# PROC051C_Decoupling_Caps_Reference.net
KiCad netlist of a schematic drawn in Altium Designer
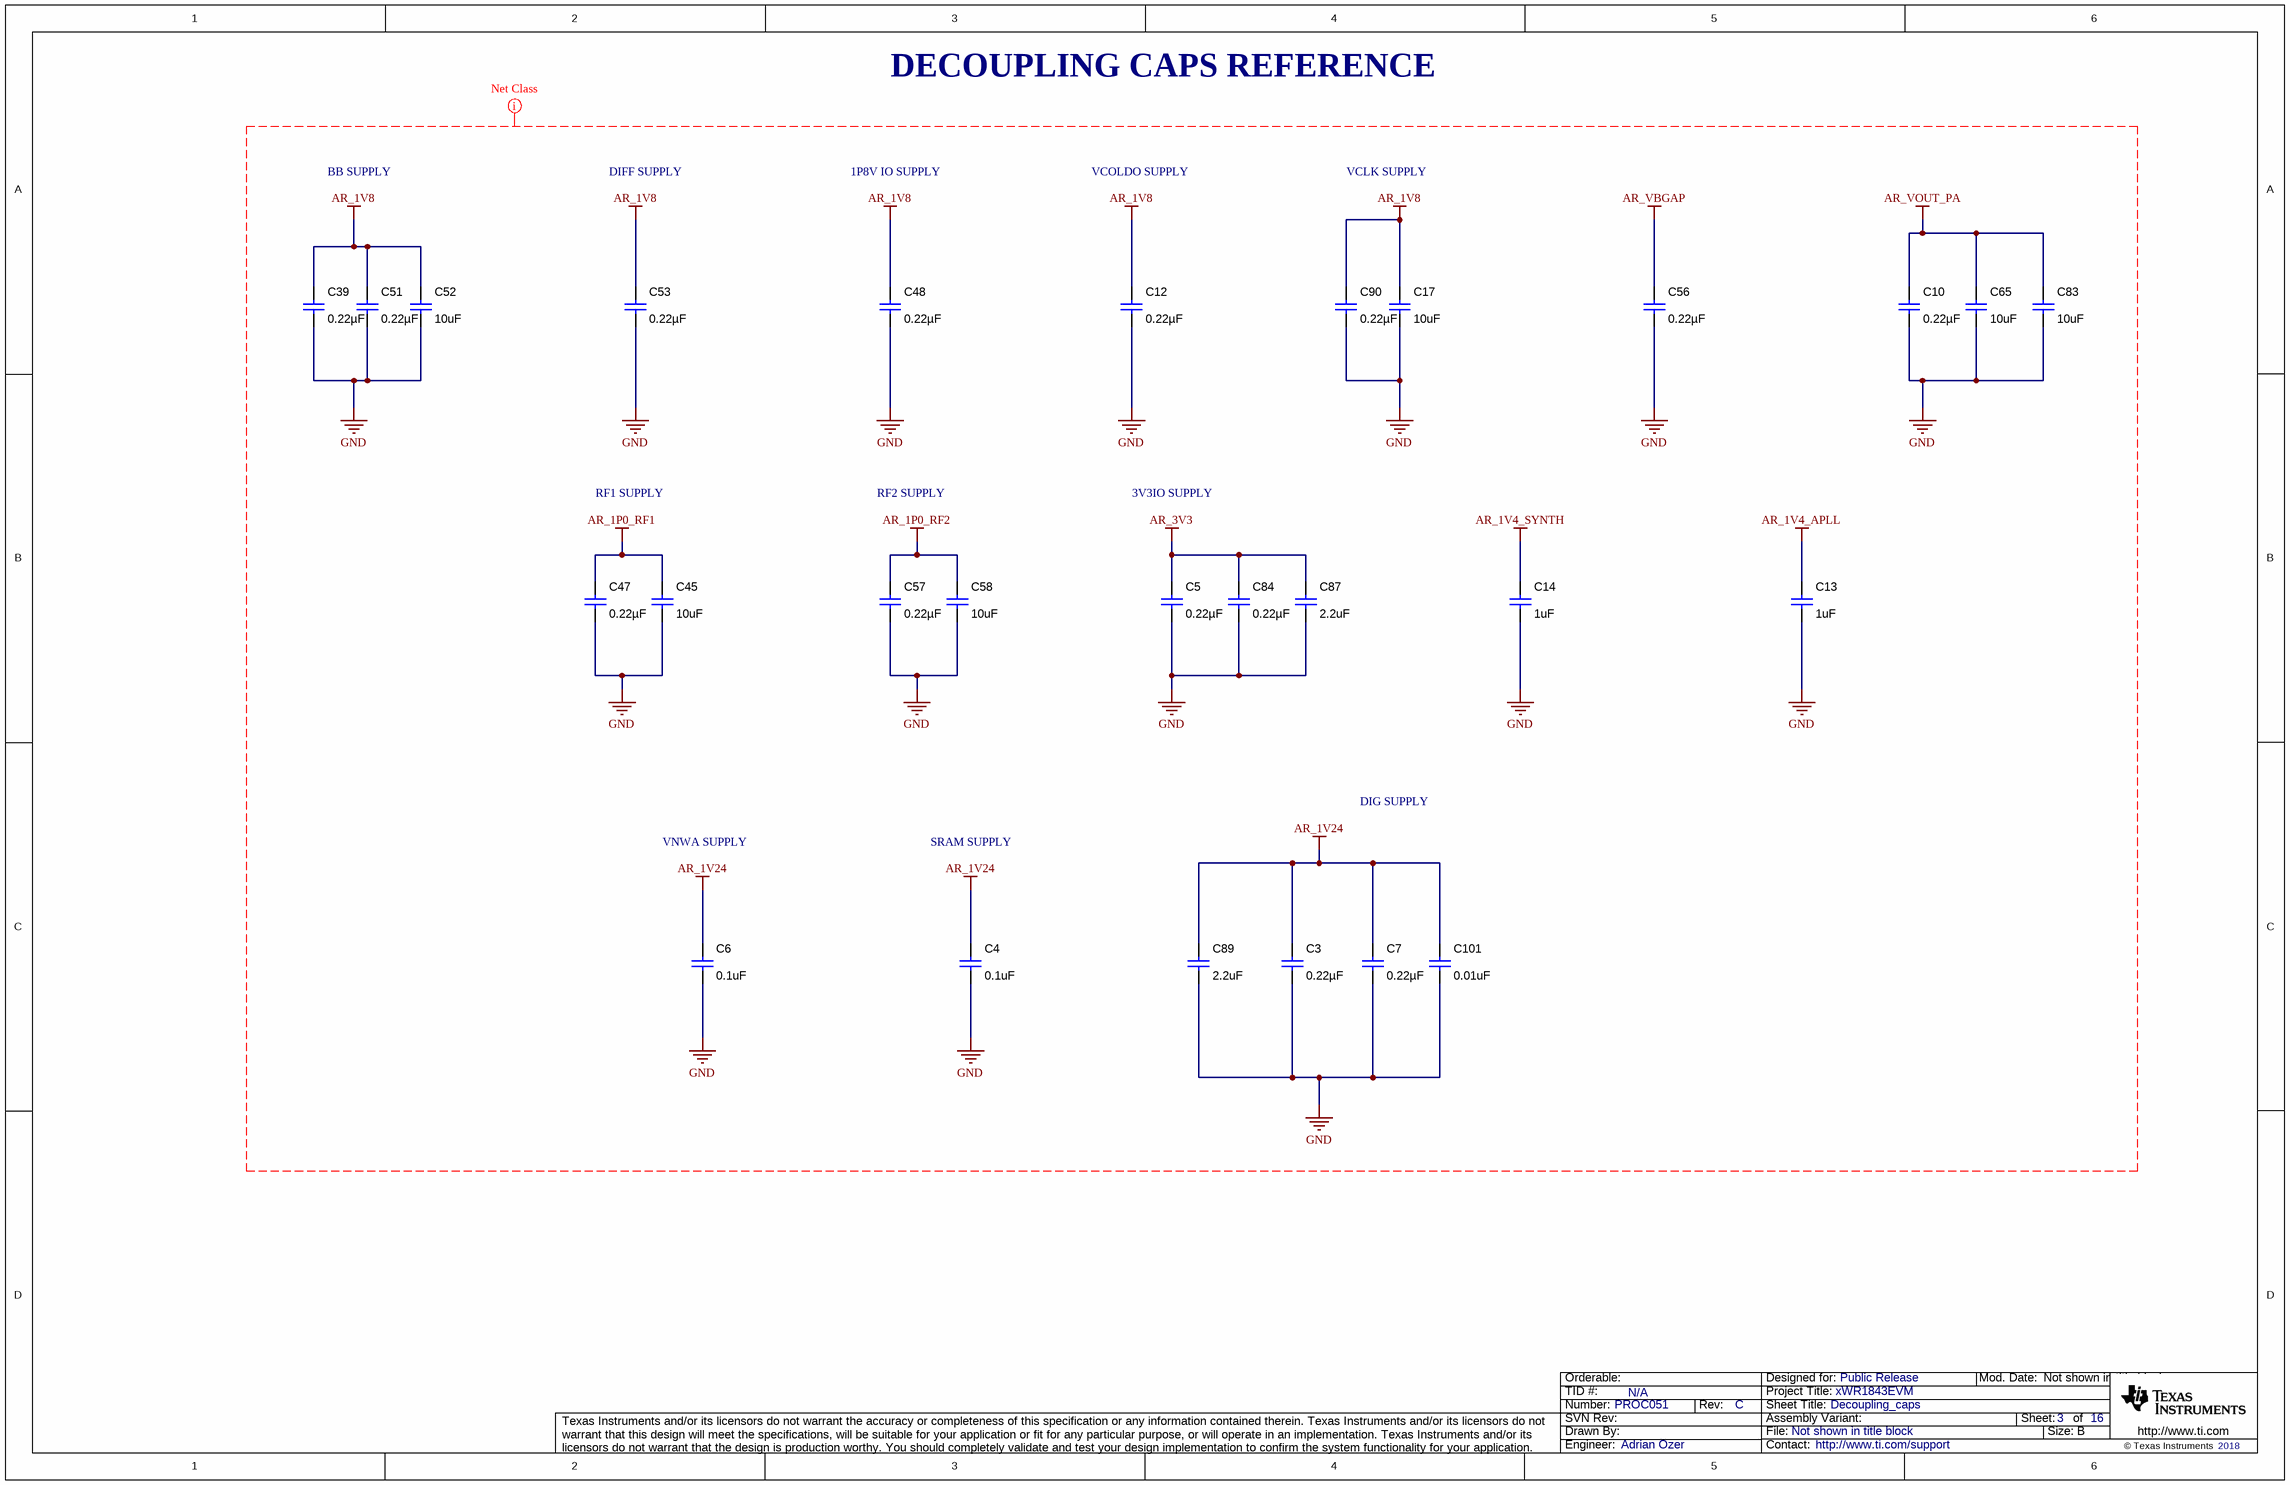
[diagram p0: PROC051C_Decoupling_Caps_Reference.SchDoc]

(export (version "E")
  (design (tool "Eeschema 10.0.6"))
  (components
    (comp (ref "C3")
      (value "GCM155R71C224KE02D")
      (footprint "0402L")
      (description "CAP, CERM, 0.22 µF, 16 V,+/- 10%, X7R, AEC-Q200 Grade 1, 0402")
      (fields (field (name "MANUFACTURER") "MuRata") (field (name "VALUEDISPLAYED") "0.22µF"))
      (libsource (lib "Altium Vault - TI") (part "CMP-0078265-1"))
    )
    (comp (ref "C4")
      (value "GCM155R71C104KA55D")
      (footprint "0402L")
      (description "CAP, CERM, 0.1 uF, 16 V, +/- 10%, X7R, 0402")
      (fields
        (field (name "MANUFACTURER") "MuRata")
        (field (name "VALUEDISPLAYED") "0.1uF")
        (field (name "PUBLISHER") "Texas Instruments")
      )
      (libsource (lib "Altium Vault - TI") (part "CMP-0006351-2"))
    )
    (comp (ref "C5")
      (value "GCM155R71C224KE02D")
      (footprint "0402L")
      (description "CAP, CERM, 0.22 µF, 16 V,+/- 10%, X7R, AEC-Q200 Grade 1, 0402")
      (fields (field (name "MANUFACTURER") "MuRata") (field (name "VALUEDISPLAYED") "0.22µF"))
      (libsource (lib "Altium Vault - TI") (part "CMP-0078265-1"))
    )
    (comp (ref "C6")
      (value "GCM155R71C104KA55D")
      (footprint "0402L")
      (description "CAP, CERM, 0.1 uF, 16 V, +/- 10%, X7R, 0402")
      (fields
        (field (name "MANUFACTURER") "MuRata")
        (field (name "VALUEDISPLAYED") "0.1uF")
        (field (name "PUBLISHER") "Texas Instruments")
      )
      (libsource (lib "Altium Vault - TI") (part "Capacitor"))
    )
    (comp (ref "C7")
      (value "GCM155R71C224KE02D")
      (footprint "0402L")
      (description "CAP, CERM, 0.22 µF, 16 V,+/- 10%, X7R, AEC-Q200 Grade 1, 0402")
      (fields (field (name "MANUFACTURER") "MuRata") (field (name "VALUEDISPLAYED") "0.22µF"))
      (libsource (lib "Altium Vault - TI") (part "CMP-0078265-1"))
    )
    (comp (ref "C10")
      (value "GCM155R71C224KE02D")
      (footprint "0402L")
      (description "CAP, CERM, 0.22 µF, 16 V,+/- 10%, X7R, AEC-Q200 Grade 1, 0402")
      (fields (field (name "MANUFACTURER") "MuRata") (field (name "VALUEDISPLAYED") "0.22µF"))
      (libsource (lib "Altium Vault - TI") (part "CMP-0078265-1"))
    )
    (comp (ref "C12")
      (value "GCM155R71C224KE02D")
      (footprint "0402L")
      (description "CAP, CERM, 0.22 µF, 16 V,+/- 10%, X7R, AEC-Q200 Grade 1, 0402")
      (fields (field (name "MANUFACTURER") "MuRata") (field (name "VALUEDISPLAYED") "0.22µF"))
      (libsource (lib "Altium Vault - TI") (part "CMP-0078265-1"))
    )
    (comp (ref "C13")
      (value "GCM188R71C105KA64D")
      (footprint "0603")
      (description "CAP, CERM, 1 uF, 16 V, +/- 10%, X7R, AEC-Q200 Grade 1, 0603")
      (fields
        (field (name "MANUFACTURER") "MuRata")
        (field (name "VALUEDISPLAYED") "1uF")
        (field (name "PUBLISHER") "Texas Instruments")
      )
      (libsource (lib "Altium Vault - TI") (part "Capacitor"))
    )
    (comp (ref "C14")
      (value "GCM188R71C105KA64D")
      (footprint "0603")
      (description "CAP, CERM, 1 uF, 16 V, +/- 10%, X7R, AEC-Q200 Grade 1, 0603")
      (fields
        (field (name "MANUFACTURER") "MuRata")
        (field (name "VALUEDISPLAYED") "1uF")
        (field (name "PUBLISHER") "Texas Instruments")
      )
      (libsource (lib "Altium Vault - TI") (part "CMP-0007136-5"))
    )
    (comp (ref "C17")
      (value "GCM21BR71A106KE22L")
      (footprint "0805_HV")
      (description "CAP, CERM, 10 uF, 10 V, +/- 10%, X7R, 0805")
      (fields
        (field (name "MANUFACTURER") "MuRata")
        (field (name "VALUEDISPLAYED") "10uF")
        (field (name "PUBLISHER") "Texas Instruments")
      )
      (libsource (lib "Altium Vault - TI") (part "CMP-0008017-2"))
    )
    (comp (ref "C39")
      (value "GCM155R71C224KE02D")
      (footprint "0402L")
      (description "CAP, CERM, 0.22 µF, 16 V,+/- 10%, X7R, AEC-Q200 Grade 1, 0402")
      (fields (field (name "MANUFACTURER") "MuRata") (field (name "VALUEDISPLAYED") "0.22µF"))
      (libsource (lib "Altium Vault - TI") (part "CMP-0078265-1"))
    )
    (comp (ref "C45")
      (value "GCM21BR71A106KE22L")
      (footprint "0805_HV")
      (description "CAP, CERM, 10 uF, 10 V, +/- 10%, X7R, 0805")
      (fields
        (field (name "MANUFACTURER") "MuRata")
        (field (name "VALUEDISPLAYED") "10uF")
        (field (name "PUBLISHER") "Texas Instruments")
      )
      (libsource (lib "Altium Vault - TI") (part "CMP-0008017-2"))
    )
    (comp (ref "C47")
      (value "GCM155R71C224KE02D")
      (footprint "0402L")
      (description "CAP, CERM, 0.22 µF, 16 V,+/- 10%, X7R, AEC-Q200 Grade 1, 0402")
      (fields (field (name "MANUFACTURER") "MuRata") (field (name "VALUEDISPLAYED") "0.22µF"))
      (libsource (lib "Altium Vault - TI") (part "CMP-0078265-1"))
    )
    (comp (ref "C48")
      (value "GCM155R71C224KE02D")
      (footprint "0402L")
      (description "CAP, CERM, 0.22 µF, 16 V,+/- 10%, X7R, AEC-Q200 Grade 1, 0402")
      (fields (field (name "MANUFACTURER") "MuRata") (field (name "VALUEDISPLAYED") "0.22µF"))
      (libsource (lib "Altium Vault - TI") (part "CMP-0078265-1"))
    )
    (comp (ref "C51")
      (value "GCM155R71C224KE02D")
      (footprint "0402L")
      (description "CAP, CERM, 0.22 µF, 16 V,+/- 10%, X7R, AEC-Q200 Grade 1, 0402")
      (fields (field (name "MANUFACTURER") "MuRata") (field (name "VALUEDISPLAYED") "0.22µF"))
      (libsource (lib "Altium Vault - TI") (part "CMP-0078265-1"))
    )
    (comp (ref "C52")
      (value "GCM21BR71A106KE22L")
      (footprint "0805_HV")
      (description "CAP, CERM, 10 uF, 10 V, +/- 10%, X7R, 0805")
      (fields
        (field (name "MANUFACTURER") "MuRata")
        (field (name "VALUEDISPLAYED") "10uF")
        (field (name "PUBLISHER") "Texas Instruments")
      )
      (libsource (lib "Altium Vault - TI") (part "CMP-0008017-2"))
    )
    (comp (ref "C53")
      (value "GCM155R71C224KE02D")
      (footprint "0402L")
      (description "CAP, CERM, 0.22 µF, 16 V,+/- 10%, X7R, AEC-Q200 Grade 1, 0402")
      (fields (field (name "MANUFACTURER") "MuRata") (field (name "VALUEDISPLAYED") "0.22µF"))
      (libsource (lib "Altium Vault - TI") (part "CMP-0078265-1"))
    )
    (comp (ref "C56")
      (value "GCM155R71C224KE02D")
      (footprint "0402L")
      (description "CAP, CERM, 0.22 µF, 16 V,+/- 10%, X7R, AEC-Q200 Grade 1, 0402")
      (fields (field (name "MANUFACTURER") "MuRata") (field (name "VALUEDISPLAYED") "0.22µF"))
      (libsource (lib "Altium Vault - TI") (part "CMP-0078265-1"))
    )
    (comp (ref "C57")
      (value "GCM155R71C224KE02D")
      (footprint "0402L")
      (description "CAP, CERM, 0.22 µF, 16 V,+/- 10%, X7R, AEC-Q200 Grade 1, 0402")
      (fields (field (name "MANUFACTURER") "MuRata") (field (name "VALUEDISPLAYED") "0.22µF"))
      (libsource (lib "Altium Vault - TI") (part "CMP-0078265-1"))
    )
    (comp (ref "C58")
      (value "GCM21BR71A106KE22L")
      (footprint "0805_HV")
      (description "CAP, CERM, 10 uF, 10 V, +/- 10%, X7R, 0805")
      (fields
        (field (name "MANUFACTURER") "MuRata")
        (field (name "VALUEDISPLAYED") "10uF")
        (field (name "PUBLISHER") "Texas Instruments")
      )
      (libsource (lib "Altium Vault - TI") (part "CMP-0008017-2"))
    )
    (comp (ref "C65")
      (value "GCM21BR71A106KE22L")
      (footprint "0805_HV")
      (description "CAP, CERM, 10 uF, 10 V, +/- 10%, X7R, 0805")
      (fields
        (field (name "MANUFACTURER") "MuRata")
        (field (name "VALUEDISPLAYED") "10uF")
        (field (name "PUBLISHER") "Texas Instruments")
      )
      (libsource (lib "Altium Vault - TI") (part "CMP-0008017-2"))
    )
    (comp (ref "C83")
      (value "GCM21BR71A106KE22L")
      (footprint "0805_HV")
      (description "CAP, CERM, 10 uF, 10 V, +/- 10%, X7R, 0805")
      (fields
        (field (name "MANUFACTURER") "MuRata")
        (field (name "VALUEDISPLAYED") "10uF")
        (field (name "PUBLISHER") "Texas Instruments")
      )
      (libsource (lib "Altium Vault - TI") (part "CMP-0008017-2"))
    )
    (comp (ref "C84")
      (value "GCM155R71C224KE02D")
      (footprint "0402L")
      (description "CAP, CERM, 0.22 µF, 16 V,+/- 10%, X7R, AEC-Q200 Grade 1, 0402")
      (fields (field (name "MANUFACTURER") "MuRata") (field (name "VALUEDISPLAYED") "0.22µF"))
      (libsource (lib "Altium Vault - TI") (part "CMP-0078265-1"))
    )
    (comp (ref "C87")
      (value "GCM188R70J225KE22D")
      (footprint "0603")
      (description "CAP, CERM, 2.2 uF, 6.3 V, +/- 10%, X7R, AEC-Q200 Grade 1, 0603")
      (fields
        (field (name "MANUFACTURER") "MuRata")
        (field (name "VALUEDISPLAYED") "2.2uF")
        (field (name "PUBLISHER") "Texas Instruments")
      )
      (libsource (lib "Altium Vault - TI") (part "Capacitor"))
    )
    (comp (ref "C89")
      (value "GCM188R70J225KE22D")
      (footprint "0603")
      (description "CAP, CERM, 2.2 uF, 6.3 V, +/- 10%, X7R, AEC-Q200 Grade 1, 0603")
      (fields
        (field (name "MANUFACTURER") "MuRata")
        (field (name "VALUEDISPLAYED") "2.2uF")
        (field (name "PUBLISHER") "Texas Instruments")
      )
      (libsource (lib "Altium Vault - TI") (part "Capacitor"))
    )
    (comp (ref "C90")
      (value "GCM155R71C224KE02D")
      (footprint "0402L")
      (description "CAP, CERM, 0.22 µF, 16 V,+/- 10%, X7R, AEC-Q200 Grade 1, 0402")
      (fields (field (name "MANUFACTURER") "MuRata") (field (name "VALUEDISPLAYED") "0.22µF"))
      (libsource (lib "Altium Vault - TI") (part "CMP-0078265-1"))
    )
    (comp (ref "C101")
      (value "GCM155R71E103KA37D")
      (footprint "0402L")
      (description "CAP, CERM, 0.01 uF, 25 V, +/- 10%, X7R, 0402")
      (fields
        (field (name "MANUFACTURER") "MuRata")
        (field (name "VALUEDISPLAYED") "0.01uF")
        (field (name "PUBLISHER") "Texas Instruments")
      )
      (libsource (lib "Altium Vault - TI") (part "CMP-0006352-2"))
    )
  )
  (nets
    (net (code "1") (name "AR_1P0_RF1") (class "Default")
      (node (ref "C45") (pin "2") (pinfunction "2_2") (pintype "passive"))
      (node (ref "C47") (pin "2") (pinfunction "2_2") (pintype "passive"))
    )
    (net (code "2") (name "AR_1P0_RF2") (class "Default")
      (node (ref "C57") (pin "2") (pinfunction "2_2") (pintype "passive"))
      (node (ref "C58") (pin "2") (pinfunction "2_2") (pintype "passive"))
    )
    (net (code "3") (name "AR_1V4_APLL") (class "Default")
      (node (ref "C13") (pin "2") (pinfunction "2_2") (pintype "passive"))
    )
    (net (code "4") (name "AR_1V4_SYNTH") (class "Default")
      (node (ref "C14") (pin "2") (pinfunction "2_2") (pintype "passive"))
    )
    (net (code "5") (name "AR_1V8") (class "Default")
      (node (ref "C12") (pin "2") (pinfunction "2_2") (pintype "passive"))
      (node (ref "C17") (pin "2") (pinfunction "2_2") (pintype "passive"))
      (node (ref "C39") (pin "2") (pinfunction "2_2") (pintype "passive"))
      (node (ref "C48") (pin "2") (pinfunction "2_2") (pintype "passive"))
      (node (ref "C51") (pin "2") (pinfunction "2_2") (pintype "passive"))
      (node (ref "C52") (pin "2") (pinfunction "2_2") (pintype "passive"))
      (node (ref "C53") (pin "2") (pinfunction "2_2") (pintype "passive"))
      (node (ref "C90") (pin "2") (pinfunction "2_2") (pintype "passive"))
    )
    (net (code "6") (name "AR_1V24") (class "Default")
      (node (ref "C101") (pin "1") (pinfunction "1_1") (pintype "passive"))
      (node (ref "C3") (pin "2") (pinfunction "2_2") (pintype "passive"))
      (node (ref "C4") (pin "2") (pinfunction "2_2") (pintype "passive"))
      (node (ref "C6") (pin "2") (pinfunction "2_2") (pintype "passive"))
      (node (ref "C7") (pin "2") (pinfunction "2_2") (pintype "passive"))
      (node (ref "C89") (pin "2") (pinfunction "2_2") (pintype "passive"))
    )
    (net (code "7") (name "AR_3V3") (class "Default")
      (node (ref "C5") (pin "2") (pinfunction "2_2") (pintype "passive"))
      (node (ref "C84") (pin "2") (pinfunction "2_2") (pintype "passive"))
      (node (ref "C87") (pin "2") (pinfunction "2_2") (pintype "passive"))
    )
    (net (code "8") (name "AR_VBGAP") (class "Default")
      (node (ref "C56") (pin "2") (pinfunction "2_2") (pintype "passive"))
    )
    (net (code "9") (name "AR_VOUT_PA") (class "Default")
      (node (ref "C10") (pin "2") (pinfunction "2_2") (pintype "passive"))
      (node (ref "C65") (pin "2") (pinfunction "2_2") (pintype "passive"))
      (node (ref "C83") (pin "2") (pinfunction "2_2") (pintype "passive"))
    )
    (net (code "10") (name "GND") (class "Default")
      (node (ref "C10") (pin "1") (pinfunction "1_1") (pintype "passive"))
      (node (ref "C101") (pin "2") (pinfunction "2_2") (pintype "passive"))
      (node (ref "C12") (pin "1") (pinfunction "1_1") (pintype "passive"))
      (node (ref "C13") (pin "1") (pinfunction "1_1") (pintype "passive"))
      (node (ref "C14") (pin "1") (pinfunction "1_1") (pintype "passive"))
      (node (ref "C17") (pin "1") (pinfunction "1_1") (pintype "passive"))
      (node (ref "C3") (pin "1") (pinfunction "1_1") (pintype "passive"))
      (node (ref "C39") (pin "1") (pinfunction "1_1") (pintype "passive"))
      (node (ref "C4") (pin "1") (pinfunction "1_1") (pintype "passive"))
      (node (ref "C45") (pin "1") (pinfunction "1_1") (pintype "passive"))
      (node (ref "C47") (pin "1") (pinfunction "1_1") (pintype "passive"))
      (node (ref "C48") (pin "1") (pinfunction "1_1") (pintype "passive"))
      (node (ref "C5") (pin "1") (pinfunction "1_1") (pintype "passive"))
      (node (ref "C51") (pin "1") (pinfunction "1_1") (pintype "passive"))
      (node (ref "C52") (pin "1") (pinfunction "1_1") (pintype "passive"))
      (node (ref "C53") (pin "1") (pinfunction "1_1") (pintype "passive"))
      (node (ref "C56") (pin "1") (pinfunction "1_1") (pintype "passive"))
      (node (ref "C57") (pin "1") (pinfunction "1_1") (pintype "passive"))
      (node (ref "C58") (pin "1") (pinfunction "1_1") (pintype "passive"))
      (node (ref "C6") (pin "1") (pinfunction "1_1") (pintype "passive"))
      (node (ref "C65") (pin "1") (pinfunction "1_1") (pintype "passive"))
      (node (ref "C7") (pin "1") (pinfunction "1_1") (pintype "passive"))
      (node (ref "C83") (pin "1") (pinfunction "1_1") (pintype "passive"))
      (node (ref "C84") (pin "1") (pinfunction "1_1") (pintype "passive"))
      (node (ref "C87") (pin "1") (pinfunction "1_1") (pintype "passive"))
      (node (ref "C89") (pin "1") (pinfunction "1_1") (pintype "passive"))
      (node (ref "C90") (pin "1") (pinfunction "1_1") (pintype "passive"))
    )
  )
)
